# IsolationBarriers.net
KiCad netlist of a schematic drawn in Altium Designer
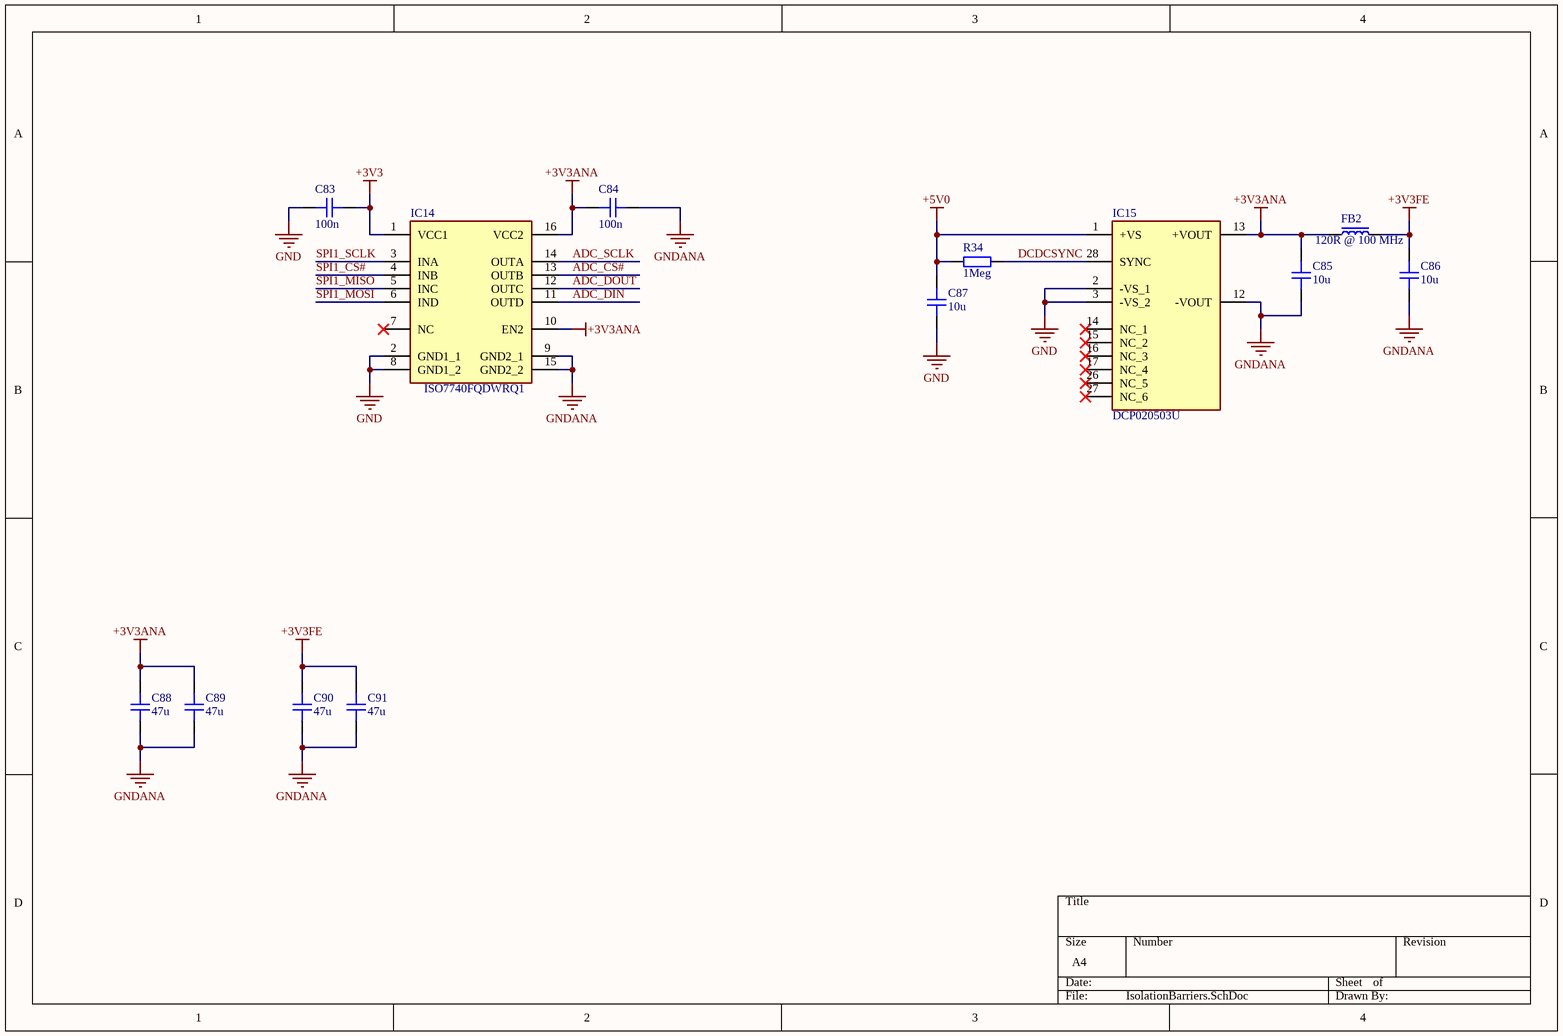
[diagram p0: IsolationBarriers.SchDoc]

(export (version "E")
  (design (tool "Eeschema 10.0.6"))
  (components
    (comp (ref "C83")
      (value "100n")
      (footprint "CAP_0402")
      (description "Capacitor SMD 0402")
      (libsource (lib "Schematic-Lib-PhilsLab") (part "CAP_0402"))
    )
    (comp (ref "C84")
      (value "100n")
      (footprint "CAP_0402")
      (description "Capacitor SMD 0402")
      (libsource (lib "Schematic-Lib-PhilsLab") (part "CAP_0402"))
    )
    (comp (ref "C85")
      (value "10u")
      (footprint "CAP_0603")
      (description "Capacitor SMD 0603")
      (libsource (lib "Schematic-Lib-PhilsLab") (part "CAP_0603"))
    )
    (comp (ref "C86")
      (value "10u")
      (footprint "CAP_0603")
      (description "Capacitor SMD 0603")
      (libsource (lib "Schematic-Lib-PhilsLab") (part "CAP_0603"))
    )
    (comp (ref "C87")
      (value "10u")
      (footprint "CAP_0603")
      (description "Capacitor SMD 0603")
      (libsource (lib "Schematic-Lib-PhilsLab") (part "CAP_0603"))
    )
    (comp (ref "C88")
      (value "47u")
      (footprint "CAP_1210")
      (description "Capacitor SMD 1210")
      (libsource (lib "Schematic-Lib-PhilsLab") (part "CAP_1210"))
    )
    (comp (ref "C89")
      (value "47u")
      (footprint "CAP_1210")
      (description "Capacitor SMD 1210")
      (libsource (lib "Schematic-Lib-PhilsLab") (part "CAP_1210"))
    )
    (comp (ref "C90")
      (value "47u")
      (footprint "CAP_1210")
      (description "Capacitor SMD 1210")
      (libsource (lib "Schematic-Lib-PhilsLab") (part "CAP_1210"))
    )
    (comp (ref "C91")
      (value "47u")
      (footprint "CAP_1210")
      (description "Capacitor SMD 1210")
      (libsource (lib "Schematic-Lib-PhilsLab") (part "CAP_1210"))
    )
    (comp (ref "FB2")
      (value "120R @ 100 MHz")
      (footprint "FB_0603")
      (description "Ferrite Bead SMD 0603")
      (libsource (lib "Schematic-Lib-PhilsLab") (part "FB_0603"))
    )
    (comp (ref "IC14")
      (value "ISO7740FQDWRQ1")
      (footprint "Footprint-Lib-PhilsLab:SOIC127P1030X265-16N")
      (description "Integrated Circuit")
      (fields (field (name "MOUSER PART NUMBER") "595-ISO7740FQDWRQ1"))
      (libsource (lib "Schematic-Lib-PhilsLab") (part "ISO7740FQDWRQ1"))
    )
    (comp (ref "IC15")
      (value "DCP020503U")
      (footprint "Footprint-Lib-PhilsLab:DVB0012A")
      (description "TI Isolated DC DC Converter")
      (fields (field (name "MOUSER PART NUMBER") "595-DCP020503U"))
      (libsource (lib "Schematic-Lib-PhilsLab") (part "DCP020503U"))
    )
    (comp (ref "R34")
      (value "1Meg")
      (footprint "RES_0402")
      (description "Resistor SMD 0402")
      (libsource (lib "Schematic-Lib-PhilsLab") (part "RES_0402"))
    )
  )
  (nets
    (net (code "1") (name "+3V3") (class "Default")
      (node (ref "C83") (pin "1") (pinfunction "1_1") (pintype "passive"))
      (node (ref "IC14") (pin "1") (pinfunction "VCC1_1") (pintype "passive"))
    )
    (net (code "2") (name "+3V3ANA") (class "Default")
      (node (ref "C84") (pin "2") (pinfunction "2_2") (pintype "passive"))
      (node (ref "C85") (pin "2") (pinfunction "2_2") (pintype "passive"))
      (node (ref "C88") (pin "2") (pinfunction "2_2") (pintype "passive"))
      (node (ref "C89") (pin "2") (pinfunction "2_2") (pintype "passive"))
      (node (ref "FB2") (pin "1") (pinfunction "1_1") (pintype "passive"))
      (node (ref "IC14") (pin "10") (pinfunction "EN2_10") (pintype "passive"))
      (node (ref "IC14") (pin "16") (pinfunction "VCC2_16") (pintype "passive"))
      (node (ref "IC15") (pin "13") (pinfunction "+VOUT_13") (pintype "passive"))
    )
    (net (code "3") (name "+3V3FE") (class "Default")
      (node (ref "C86") (pin "2") (pinfunction "2_2") (pintype "passive"))
      (node (ref "C90") (pin "2") (pinfunction "2_2") (pintype "passive"))
      (node (ref "C91") (pin "2") (pinfunction "2_2") (pintype "passive"))
      (node (ref "FB2") (pin "2") (pinfunction "2_2") (pintype "passive"))
    )
    (net (code "4") (name "+5V0") (class "Default")
      (node (ref "C87") (pin "2") (pinfunction "2_2") (pintype "passive"))
      (node (ref "IC15") (pin "1") (pinfunction "+VS_1") (pintype "passive"))
      (node (ref "R34") (pin "1") (pinfunction "1_1") (pintype "passive"))
    )
    (net (code "5") (name "/ADC_CS#") (class "Default")
      (node (ref "IC14") (pin "13") (pinfunction "OUTB_13") (pintype "passive"))
    )
    (net (code "6") (name "/ADC_DIN") (class "Default")
      (node (ref "IC14") (pin "11") (pinfunction "OUTD_11") (pintype "passive"))
    )
    (net (code "7") (name "/ADC_DOUT") (class "Default")
      (node (ref "IC14") (pin "12") (pinfunction "OUTC_12") (pintype "passive"))
    )
    (net (code "8") (name "/ADC_SCLK") (class "Default")
      (node (ref "IC14") (pin "14") (pinfunction "OUTA_14") (pintype "passive"))
    )
    (net (code "9") (name "/DCDCSYNC") (class "Default")
      (node (ref "IC15") (pin "28") (pinfunction "SYNC_28") (pintype "passive"))
      (node (ref "R34") (pin "2") (pinfunction "2_2") (pintype "passive"))
    )
    (net (code "10") (name "/SPI1_CS#") (class "Default")
      (node (ref "IC14") (pin "4") (pinfunction "INB_4") (pintype "passive"))
    )
    (net (code "11") (name "/SPI1_MISO") (class "Default")
      (node (ref "IC14") (pin "5") (pinfunction "INC_5") (pintype "passive"))
    )
    (net (code "12") (name "/SPI1_MOSI") (class "Default")
      (node (ref "IC14") (pin "6") (pinfunction "IND_6") (pintype "passive"))
    )
    (net (code "13") (name "/SPI1_SCLK") (class "Default")
      (node (ref "IC14") (pin "3") (pinfunction "INA_3") (pintype "passive"))
    )
    (net (code "14") (name "GND") (class "Default")
      (node (ref "C83") (pin "2") (pinfunction "2_2") (pintype "passive"))
      (node (ref "C87") (pin "1") (pinfunction "1_1") (pintype "passive"))
      (node (ref "IC14") (pin "2") (pinfunction "GND1_1_2") (pintype "passive"))
      (node (ref "IC14") (pin "8") (pinfunction "GND1_2_8") (pintype "passive"))
      (node (ref "IC15") (pin "2") (pinfunction "-VS_1_2") (pintype "passive"))
      (node (ref "IC15") (pin "3") (pinfunction "-VS_2_3") (pintype "passive"))
    )
    (net (code "15") (name "GNDANA") (class "Default")
      (node (ref "C84") (pin "1") (pinfunction "1_1") (pintype "passive"))
      (node (ref "C85") (pin "1") (pinfunction "1_1") (pintype "passive"))
      (node (ref "C86") (pin "1") (pinfunction "1_1") (pintype "passive"))
      (node (ref "C88") (pin "1") (pinfunction "1_1") (pintype "passive"))
      (node (ref "C89") (pin "1") (pinfunction "1_1") (pintype "passive"))
      (node (ref "C90") (pin "1") (pinfunction "1_1") (pintype "passive"))
      (node (ref "C91") (pin "1") (pinfunction "1_1") (pintype "passive"))
      (node (ref "IC14") (pin "15") (pinfunction "GND2_2_15") (pintype "passive"))
      (node (ref "IC14") (pin "9") (pinfunction "GND2_1_9") (pintype "passive"))
      (node (ref "IC15") (pin "12") (pinfunction "-VOUT_12") (pintype "passive"))
    )
    (net (code "16") (name "unconnected-(IC14-NC-Pad7)") (class "Default")
      (node (ref "IC14") (pin "7") (pinfunction "NC_7") (pintype "passive+no_connect"))
    )
    (net (code "17") (name "unconnected-(IC15-NC_1-Pad14)") (class "Default")
      (node (ref "IC15") (pin "14") (pinfunction "NC_1_14") (pintype "passive+no_connect"))
    )
    (net (code "18") (name "unconnected-(IC15-NC_2-Pad15)") (class "Default")
      (node (ref "IC15") (pin "15") (pinfunction "NC_2_15") (pintype "passive+no_connect"))
    )
    (net (code "19") (name "unconnected-(IC15-NC_3-Pad16)") (class "Default")
      (node (ref "IC15") (pin "16") (pinfunction "NC_3_16") (pintype "passive+no_connect"))
    )
    (net (code "20") (name "unconnected-(IC15-NC_4-Pad17)") (class "Default")
      (node (ref "IC15") (pin "17") (pinfunction "NC_4_17") (pintype "passive+no_connect"))
    )
    (net (code "21") (name "unconnected-(IC15-NC_5-Pad26)") (class "Default")
      (node (ref "IC15") (pin "26") (pinfunction "NC_5_26") (pintype "passive+no_connect"))
    )
    (net (code "22") (name "unconnected-(IC15-NC_6-Pad27)") (class "Default")
      (node (ref "IC15") (pin "27") (pinfunction "NC_6_27") (pintype "passive+no_connect"))
    )
  )
)
